# Opto-coupler_OM.net
KiCad netlist of a schematic drawn in EAGLE
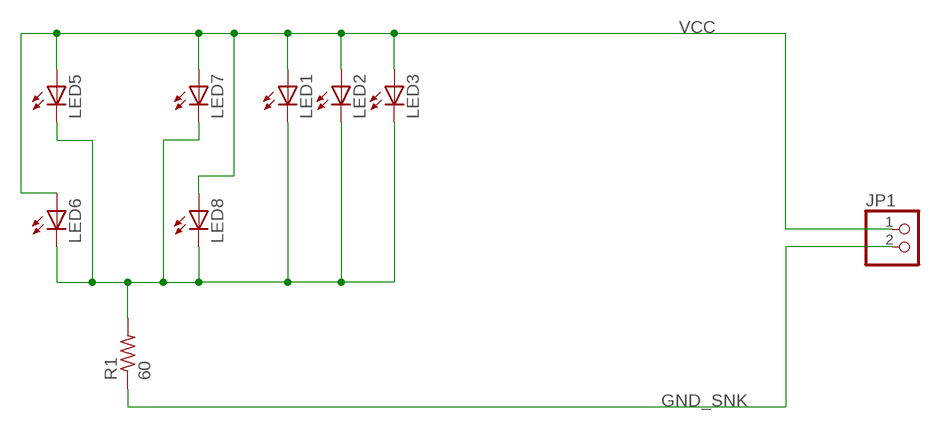
[diagram p0: schematic, sheet 1]

(export (version "E")
  (design (tool "Eeschema 10.0.6"))
  (components
    (comp (ref "JP1")
      (value "PINHD-1X2")
      (footprint "eagle-import:1X02")
      (libsource (lib "eagle-import") (part "PINHD-1X2"))
    )
    (comp (ref "LED1")
      (value "LED3MM")
      (footprint "eagle-import:LED3MM")
      (libsource (lib "eagle-import") (part "LED3MM"))
    )
    (comp (ref "LED2")
      (value "LED3MM")
      (footprint "eagle-import:LED3MM")
      (libsource (lib "eagle-import") (part "LED3MM"))
    )
    (comp (ref "LED3")
      (value "LED3MM")
      (footprint "eagle-import:LED3MM")
      (libsource (lib "eagle-import") (part "LED3MM"))
    )
    (comp (ref "LED5")
      (value "LED3MM")
      (footprint "eagle-import:LED3MM")
      (libsource (lib "eagle-import") (part "LED3MM"))
    )
    (comp (ref "LED6")
      (value "LED3MM")
      (footprint "eagle-import:LED3MM")
      (libsource (lib "eagle-import") (part "LED3MM"))
    )
    (comp (ref "LED7")
      (value "LED3MM")
      (footprint "eagle-import:LED3MM")
      (libsource (lib "eagle-import") (part "LED3MM"))
    )
    (comp (ref "LED8")
      (value "LED3MM")
      (footprint "eagle-import:LED3MM")
      (libsource (lib "eagle-import") (part "LED3MM"))
    )
    (comp (ref "R1")
      (value "60")
      (footprint "eagle-import:0204_7")
      (libsource (lib "eagle-import") (part "R-US_0204/7"))
    )
  )
  (nets
    (net (code "1") (name "/GND_SNK") (class "Default")
      (node (ref "JP1") (pin "2") (pinfunction "2_2") (pintype "passive"))
      (node (ref "R1") (pin "1") (pinfunction "1_1") (pintype "passive"))
    )
    (net (code "2") (name "/VCC") (class "Default")
      (node (ref "JP1") (pin "1") (pinfunction "1_1") (pintype "passive"))
      (node (ref "LED1") (pin "A") (pinfunction "A_A") (pintype "passive"))
      (node (ref "LED2") (pin "A") (pinfunction "A_A") (pintype "passive"))
      (node (ref "LED3") (pin "A") (pinfunction "A_A") (pintype "passive"))
      (node (ref "LED5") (pin "A") (pinfunction "A_A") (pintype "passive"))
      (node (ref "LED6") (pin "A") (pinfunction "A_A") (pintype "passive"))
      (node (ref "LED7") (pin "A") (pinfunction "A_A") (pintype "passive"))
      (node (ref "LED8") (pin "A") (pinfunction "A_A") (pintype "passive"))
    )
    (net (code "3") (name "Net-(LED1-C)") (class "Default")
      (node (ref "LED1") (pin "K") (pinfunction "C_K") (pintype "passive"))
      (node (ref "LED2") (pin "K") (pinfunction "C_K") (pintype "passive"))
      (node (ref "LED3") (pin "K") (pinfunction "C_K") (pintype "passive"))
      (node (ref "LED5") (pin "K") (pinfunction "C_K") (pintype "passive"))
      (node (ref "LED6") (pin "K") (pinfunction "C_K") (pintype "passive"))
      (node (ref "LED7") (pin "K") (pinfunction "C_K") (pintype "passive"))
      (node (ref "LED8") (pin "K") (pinfunction "C_K") (pintype "passive"))
      (node (ref "R1") (pin "2") (pinfunction "2_2") (pintype "passive"))
    )
  )
)
